# 2LD-17-mk-1_2_1.net
KiCad netlist of a schematic drawn in EAGLE
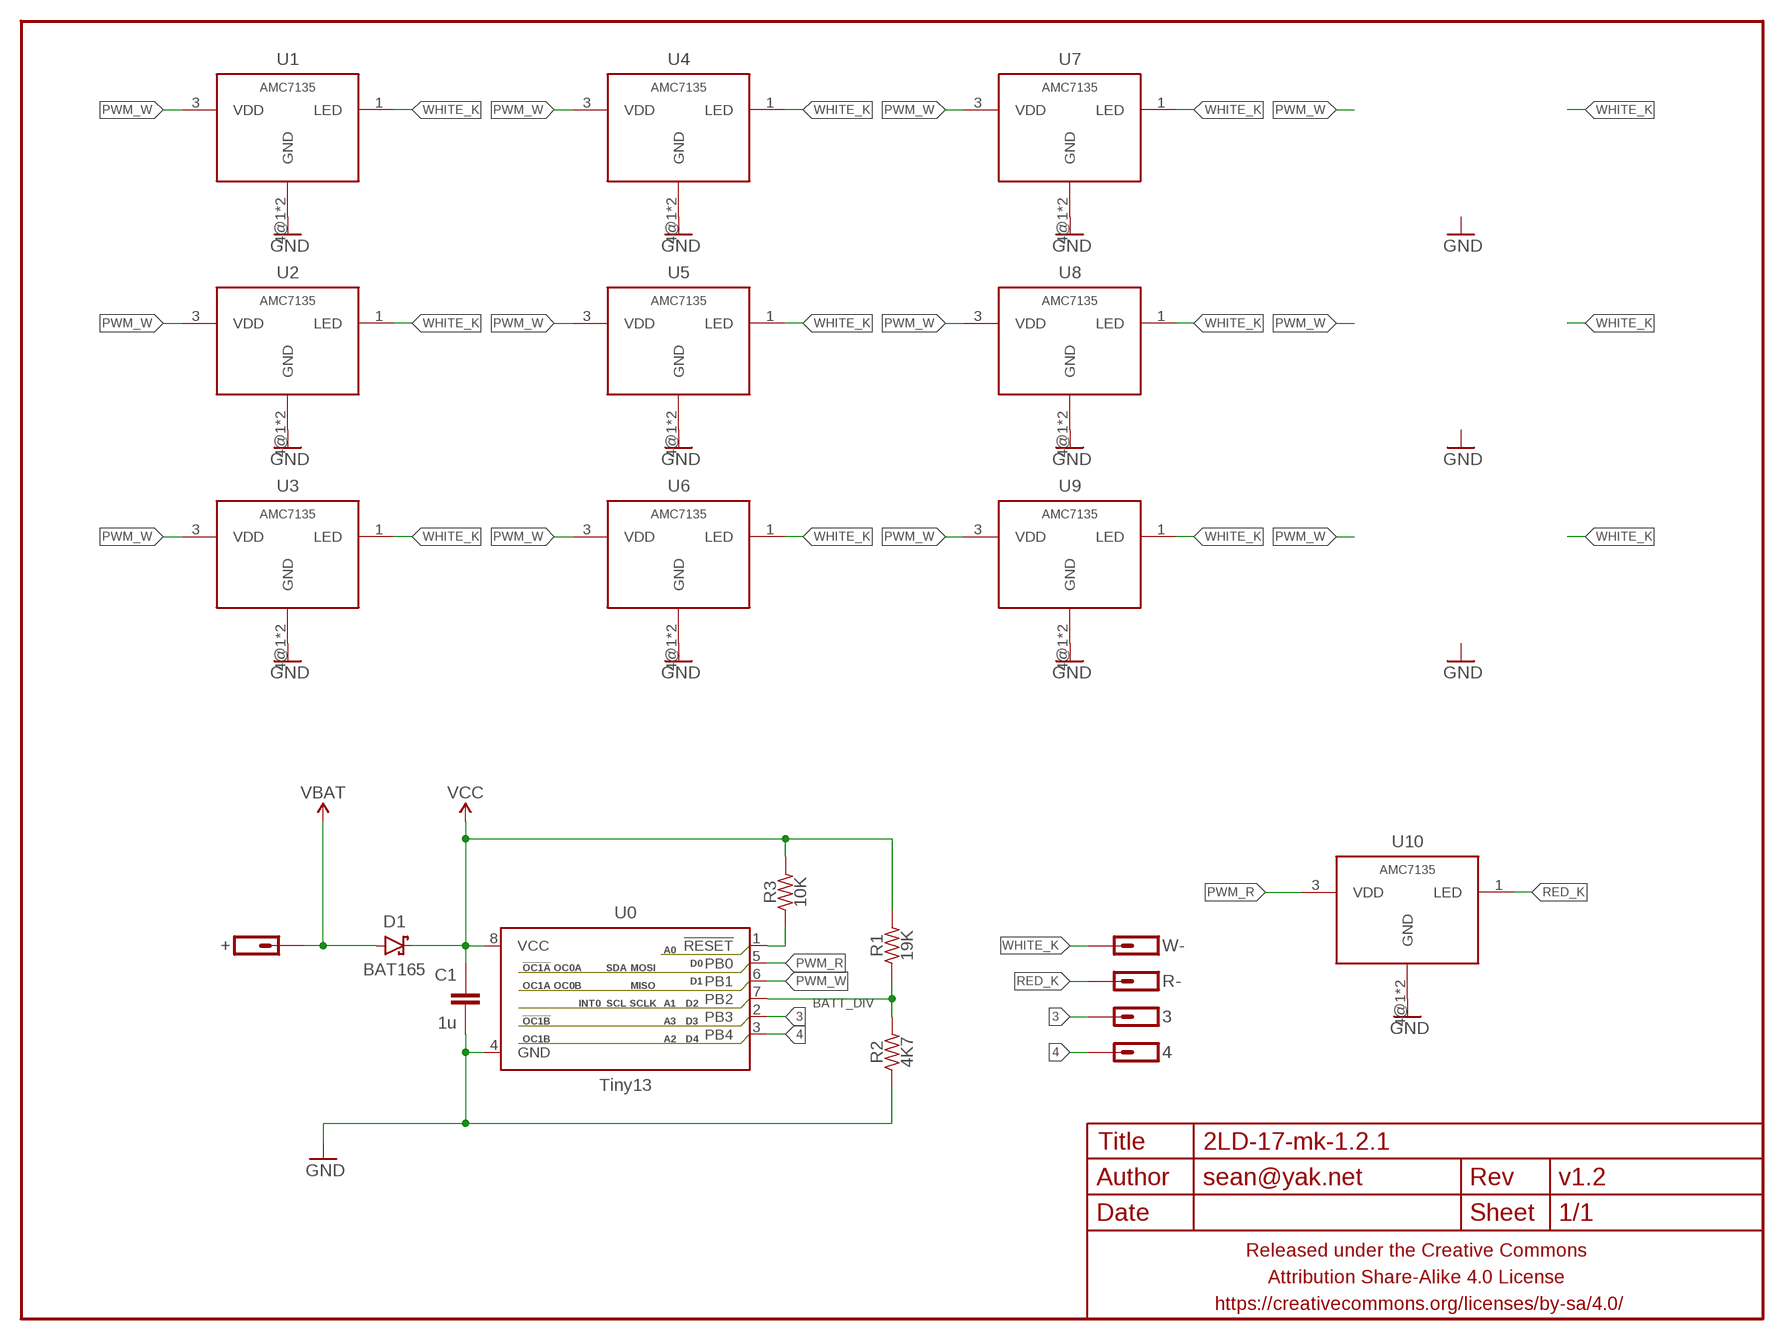
[diagram p0: schematic, sheet 1]

(export (version "E")
  (design (tool "Eeschema 10.0.6"))
  (components
    (comp (ref "+")
      (value "M01PTH-1.2MM-NS")
      (footprint "eagle-import:1X01-1.2MM-NS")
      (libsource (lib "eagle-import") (part "M01PTH-1.2MM-NS"))
    )
    (comp (ref "3")
      (value "M01SMD-1MM-DIA-NS")
      (footprint "eagle-import:1X01-SMD-1MM-DIA-NS")
      (libsource (lib "eagle-import") (part "M01SMD-1MM-DIA-NS"))
    )
    (comp (ref "4")
      (value "M01SMD-1MM-DIA-NS")
      (footprint "eagle-import:1X01-SMD-1MM-DIA-NS")
      (libsource (lib "eagle-import") (part "M01SMD-1MM-DIA-NS"))
    )
    (comp (ref "C1")
      (value "1u")
      (footprint "eagle-import:C0402")
      (libsource (lib "eagle-import") (part "CAPACITOR-CERAMICC0402"))
    )
    (comp (ref "D1")
      (value "BAT165")
      (footprint "eagle-import:SOD323-SCHOTTKY")
      (libsource (lib "eagle-import") (part "DIODE-SCHOTTKYSOD323"))
    )
    (comp (ref "FRAME1")
      (value "FRAME-LETTERNO_PACKAGE")
      (footprint "eagle-import:DUMMY")
      (fields (field (name "DESIGNER") "sean@yak.net") (field (name "VERSION") "v1.2"))
      (libsource (lib "eagle-import") (part "FRAME-LETTERNO_PACKAGE"))
    )
    (comp (ref "R-")
      (value "M01SMD-1.25MM-DIA")
      (footprint "eagle-import:1X01-SMD-1.25MM-DIA-NS")
      (libsource (lib "eagle-import") (part "M01SMD-1.25MM-DIA"))
    )
    (comp (ref "R1")
      (value "19K")
      (footprint "eagle-import:R0402")
      (libsource (lib "eagle-import") (part "RESISTORR0402"))
    )
    (comp (ref "R2")
      (value "4K7")
      (footprint "eagle-import:R0402")
      (libsource (lib "eagle-import") (part "RESISTORR0402"))
    )
    (comp (ref "R3")
      (value "10K")
      (footprint "eagle-import:R0402")
      (libsource (lib "eagle-import") (part "RESISTORR0402"))
    )
    (comp (ref "U0")
      (value "Tiny13")
      (footprint "eagle-import:SO08-NARROWER")
      (libsource (lib "eagle-import") (part "ATTINY13SOIC-NARROWPADS"))
    )
    (comp (ref "U1")
      (value "AMC7135")
      (footprint "eagle-import:SOT89-NOTHERM-ROUNDED")
      (libsource (lib "eagle-import") (part "AMC7135SOT-89-NOTHERM-ROUNDED"))
    )
    (comp (ref "U2")
      (value "AMC7135")
      (footprint "eagle-import:SOT89-NOTHERM-ROUNDED")
      (libsource (lib "eagle-import") (part "AMC7135SOT-89-NOTHERM-ROUNDED"))
    )
    (comp (ref "U3")
      (value "AMC7135")
      (footprint "eagle-import:SOT89-NOTHERM-ROUNDED")
      (libsource (lib "eagle-import") (part "AMC7135SOT-89-NOTHERM-ROUNDED"))
    )
    (comp (ref "U4")
      (value "AMC7135")
      (footprint "eagle-import:SOT89-NOTHERM-ROUNDED")
      (libsource (lib "eagle-import") (part "AMC7135SOT-89-NOTHERM-ROUNDED"))
    )
    (comp (ref "U5")
      (value "AMC7135")
      (footprint "eagle-import:SOT89-NOTHERM-ROUNDED")
      (libsource (lib "eagle-import") (part "AMC7135SOT-89-NOTHERM-ROUNDED"))
    )
    (comp (ref "U6")
      (value "AMC7135")
      (footprint "eagle-import:SOT89-NOTHERM-ROUNDED")
      (libsource (lib "eagle-import") (part "AMC7135SOT-89-NOTHERM-ROUNDED"))
    )
    (comp (ref "U7")
      (value "AMC7135")
      (footprint "eagle-import:SOT89-NOTHERM-ROUNDED")
      (libsource (lib "eagle-import") (part "AMC7135SOT-89-NOTHERM-ROUNDED"))
    )
    (comp (ref "U8")
      (value "AMC7135")
      (footprint "eagle-import:SOT89-NOTHERM-ROUNDED")
      (libsource (lib "eagle-import") (part "AMC7135SOT-89-NOTHERM-ROUNDED"))
    )
    (comp (ref "U9")
      (value "AMC7135")
      (footprint "eagle-import:SOT89-NOTHERM-ROUNDED")
      (libsource (lib "eagle-import") (part "AMC7135SOT-89-NOTHERM-ROUNDED"))
    )
    (comp (ref "U10")
      (value "AMC7135")
      (footprint "eagle-import:SOT89-NOTHERM-ROUNDED")
      (libsource (lib "eagle-import") (part "AMC7135SOT-89-NOTHERM-ROUNDED"))
    )
    (comp (ref "W-")
      (value "M01SMD-1.5MM-DIA-NS")
      (footprint "eagle-import:1X01-SMD-1.5MM-DIA-NS")
      (libsource (lib "eagle-import") (part "M01SMD-1.5MM-DIA-NS"))
    )
  )
  (nets
    (net (code "1") (name "/BATT_DIV") (class "Default")
      (node (ref "R1") (pin "1") (pinfunction "1_1") (pintype "passive"))
      (node (ref "R2") (pin "2") (pinfunction "2_2") (pintype "passive"))
      (node (ref "U0") (pin "7") (pinfunction "PB2_7") (pintype "bidirectional"))
    )
    (net (code "2") (name "3") (class "Default")
      (node (ref "3") (pin "P$1") (pinfunction "1_P$1") (pintype "passive"))
      (node (ref "U0") (pin "2") (pinfunction "PB3_2") (pintype "bidirectional"))
    )
    (net (code "3") (name "4") (class "Default")
      (node (ref "4") (pin "P$1") (pinfunction "1_P$1") (pintype "passive"))
      (node (ref "U0") (pin "3") (pinfunction "PB4_3") (pintype "bidirectional"))
    )
    (net (code "4") (name "GND") (class "Default")
      (node (ref "C1") (pin "2") (pinfunction "2_2") (pintype "passive"))
      (node (ref "R2") (pin "1") (pinfunction "1_1") (pintype "passive"))
      (node (ref "U0") (pin "4") (pinfunction "GND_4") (pintype "bidirectional"))
      (node (ref "U1") (pin "4@1") (pinfunction "GND_4@1") (pintype "bidirectional"))
      (node (ref "U1") (pin "4@2") (pinfunction "GND_4@2") (pintype "bidirectional"))
      (node (ref "U10") (pin "4@1") (pinfunction "GND_4@1") (pintype "bidirectional"))
      (node (ref "U10") (pin "4@2") (pinfunction "GND_4@2") (pintype "bidirectional"))
      (node (ref "U2") (pin "4@1") (pinfunction "GND_4@1") (pintype "bidirectional"))
      (node (ref "U2") (pin "4@2") (pinfunction "GND_4@2") (pintype "bidirectional"))
      (node (ref "U3") (pin "4@1") (pinfunction "GND_4@1") (pintype "bidirectional"))
      (node (ref "U3") (pin "4@2") (pinfunction "GND_4@2") (pintype "bidirectional"))
      (node (ref "U4") (pin "4@1") (pinfunction "GND_4@1") (pintype "bidirectional"))
      (node (ref "U4") (pin "4@2") (pinfunction "GND_4@2") (pintype "bidirectional"))
      (node (ref "U5") (pin "4@1") (pinfunction "GND_4@1") (pintype "bidirectional"))
      (node (ref "U5") (pin "4@2") (pinfunction "GND_4@2") (pintype "bidirectional"))
      (node (ref "U6") (pin "4@1") (pinfunction "GND_4@1") (pintype "bidirectional"))
      (node (ref "U6") (pin "4@2") (pinfunction "GND_4@2") (pintype "bidirectional"))
      (node (ref "U7") (pin "4@1") (pinfunction "GND_4@1") (pintype "bidirectional"))
      (node (ref "U7") (pin "4@2") (pinfunction "GND_4@2") (pintype "bidirectional"))
      (node (ref "U8") (pin "4@1") (pinfunction "GND_4@1") (pintype "bidirectional"))
      (node (ref "U8") (pin "4@2") (pinfunction "GND_4@2") (pintype "bidirectional"))
      (node (ref "U9") (pin "4@1") (pinfunction "GND_4@1") (pintype "bidirectional"))
      (node (ref "U9") (pin "4@2") (pinfunction "GND_4@2") (pintype "bidirectional"))
    )
    (net (code "5") (name "Net-(U0-~{RESET})") (class "Default")
      (node (ref "R3") (pin "1") (pinfunction "1_1") (pintype "passive"))
      (node (ref "U0") (pin "1") (pinfunction "~{RESET}_1") (pintype "bidirectional"))
    )
    (net (code "6") (name "PWM_R") (class "Default")
      (node (ref "U0") (pin "5") (pinfunction "PB0_5") (pintype "bidirectional"))
      (node (ref "U10") (pin "3") (pinfunction "VDD_3") (pintype "bidirectional"))
    )
    (net (code "7") (name "PWM_W") (class "Default")
      (node (ref "U0") (pin "6") (pinfunction "PB1_6") (pintype "bidirectional"))
      (node (ref "U1") (pin "3") (pinfunction "VDD_3") (pintype "bidirectional"))
      (node (ref "U2") (pin "3") (pinfunction "VDD_3") (pintype "bidirectional"))
      (node (ref "U3") (pin "3") (pinfunction "VDD_3") (pintype "bidirectional"))
      (node (ref "U4") (pin "3") (pinfunction "VDD_3") (pintype "bidirectional"))
      (node (ref "U5") (pin "3") (pinfunction "VDD_3") (pintype "bidirectional"))
      (node (ref "U6") (pin "3") (pinfunction "VDD_3") (pintype "bidirectional"))
      (node (ref "U7") (pin "3") (pinfunction "VDD_3") (pintype "bidirectional"))
      (node (ref "U8") (pin "3") (pinfunction "VDD_3") (pintype "bidirectional"))
      (node (ref "U9") (pin "3") (pinfunction "VDD_3") (pintype "bidirectional"))
    )
    (net (code "8") (name "RED_K") (class "Default")
      (node (ref "R-") (pin "P$1") (pinfunction "1_P$1") (pintype "passive"))
      (node (ref "U10") (pin "1") (pinfunction "LED_1") (pintype "bidirectional"))
    )
    (net (code "9") (name "VBAT") (class "Default")
      (node (ref "+") (pin "P$1") (pinfunction "1_P$1") (pintype "passive"))
      (node (ref "D1") (pin "A") (pinfunction "A_A") (pintype "passive"))
    )
    (net (code "10") (name "VCC") (class "Default")
      (node (ref "C1") (pin "1") (pinfunction "1_1") (pintype "passive"))
      (node (ref "D1") (pin "C") (pinfunction "C_C") (pintype "passive"))
      (node (ref "R1") (pin "2") (pinfunction "2_2") (pintype "passive"))
      (node (ref "R3") (pin "2") (pinfunction "2_2") (pintype "passive"))
      (node (ref "U0") (pin "8") (pinfunction "VCC_8") (pintype "bidirectional"))
    )
    (net (code "11") (name "WHITE_K") (class "Default")
      (node (ref "U1") (pin "1") (pinfunction "LED_1") (pintype "bidirectional"))
      (node (ref "U2") (pin "1") (pinfunction "LED_1") (pintype "bidirectional"))
      (node (ref "U3") (pin "1") (pinfunction "LED_1") (pintype "bidirectional"))
      (node (ref "U4") (pin "1") (pinfunction "LED_1") (pintype "bidirectional"))
      (node (ref "U5") (pin "1") (pinfunction "LED_1") (pintype "bidirectional"))
      (node (ref "U6") (pin "1") (pinfunction "LED_1") (pintype "bidirectional"))
      (node (ref "U7") (pin "1") (pinfunction "LED_1") (pintype "bidirectional"))
      (node (ref "U8") (pin "1") (pinfunction "LED_1") (pintype "bidirectional"))
      (node (ref "U9") (pin "1") (pinfunction "LED_1") (pintype "bidirectional"))
      (node (ref "W-") (pin "P$1") (pinfunction "1_P$1") (pintype "passive"))
    )
  )
)
